# ActiveRectifier_IR1167.net
KiCad netlist of a schematic drawn in Altium Designer
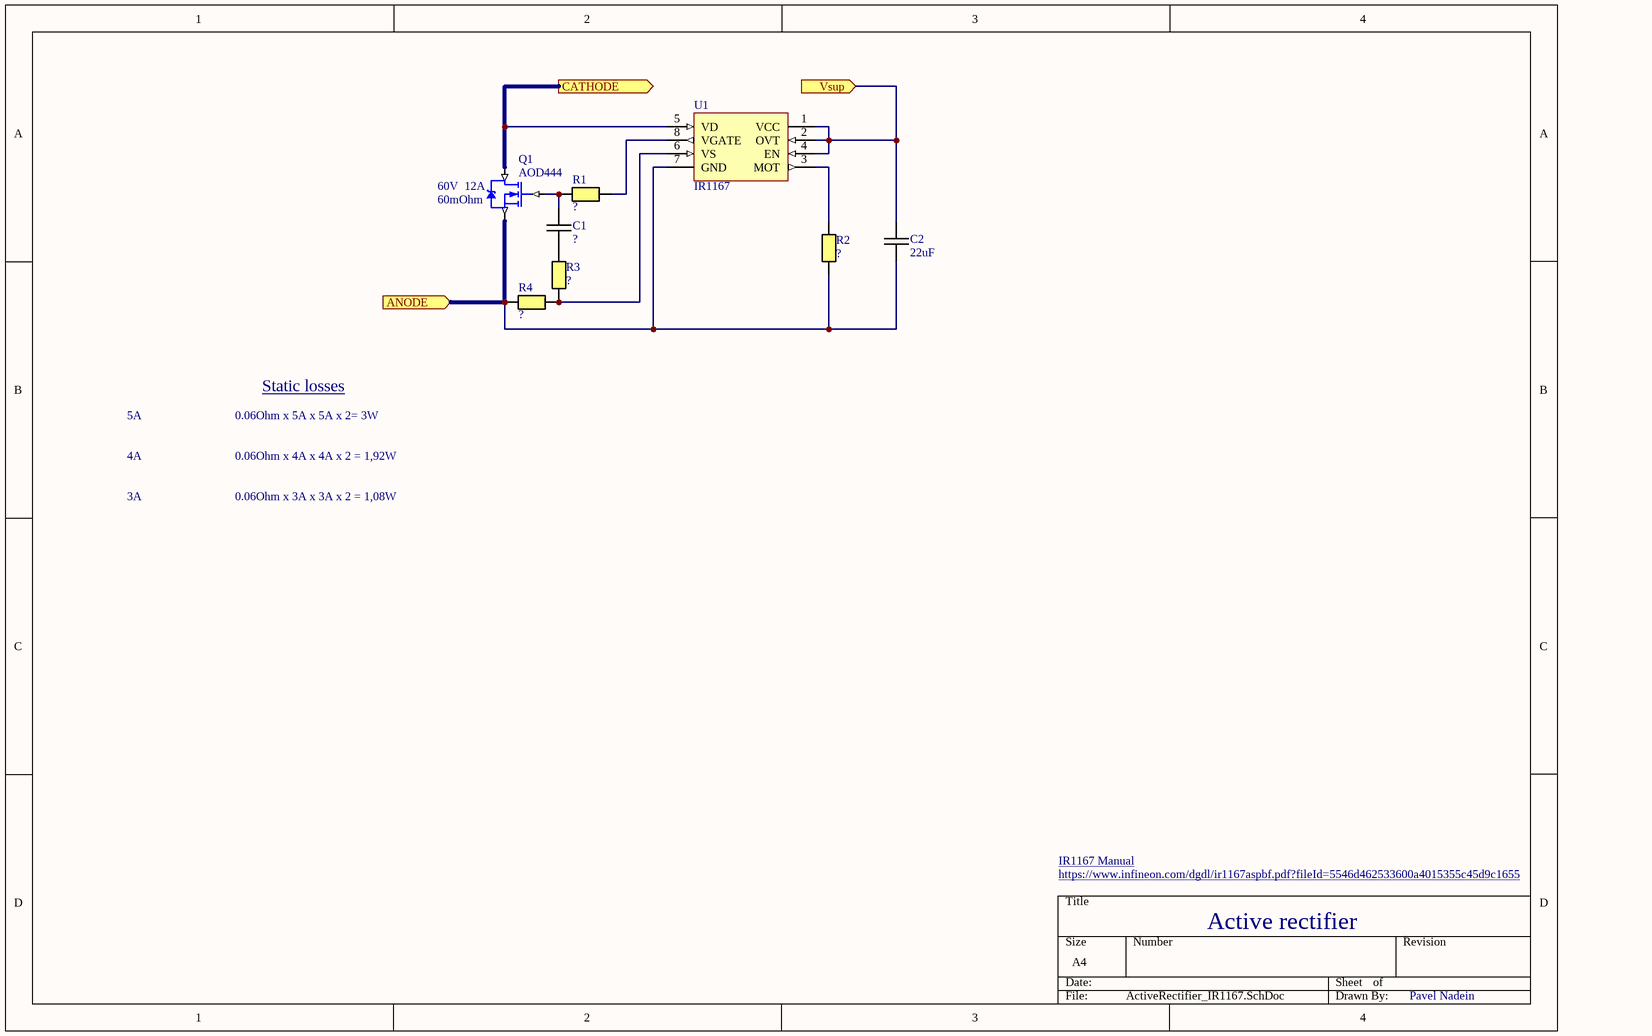
[diagram p0: ActiveRectifier_IR1167.SchDoc]

(export (version "E")
  (design (tool "Eeschema 10.0.6"))
  (components
    (comp (ref "C1")
      (value "?")
      (footprint "CAPC0603(1608)55_N")
      (description "Ceramic capacitor Medium density")
      (libsource (lib "Discrete_Passive_RCL") (part "Capacitor M"))
    )
    (comp (ref "C2")
      (value "22uF")
      (footprint "CAPC0805(2012)75_N")
      (description "Ceramic capacitor Medium density")
      (libsource (lib "Discrete_Passive_RCL") (part "Capacitor M"))
    )
    (comp (ref "Q1")
      (value "AOD444")
      (footprint "TO-252")
      (description "HEXFET Power MOSFET")
      (fields (field (name "VDS") "60V") (field (name "ID") "12A") (field (name "RDS") "60mOhm"))
      (libsource (lib "Transistors") (part "AOD444"))
    )
    (comp (ref "R1")
      (value "?")
      (footprint "RESC0603(1608)_N")
      (description "Resistor Medium Density")
      (libsource (lib "") (part "Resistor M_2"))
    )
    (comp (ref "R2")
      (value "?")
      (footprint "RESC0603(1608)_N")
      (description "Resistor Medium Density")
      (libsource (lib "") (part "Resistor M_1"))
    )
    (comp (ref "R3")
      (value "?")
      (footprint "RESC0603(1608)_N")
      (description "Resistor Medium Density")
      (libsource (lib "Discrete_Passive_RCL") (part "Resistor M"))
    )
    (comp (ref "R4")
      (value "?")
      (footprint "RESC0603(1608)_N")
      (description "Resistor Medium Density")
      (libsource (lib "") (part "Resistor M_2"))
    )
    (comp (ref "U1")
      (value "IR1167")
      (footprint "SOIC8_N")
      (description "Secondary side high speed SR controller")
      (libsource (lib "IntegrationCircuits") (part "IR1167"))
    )
  )
  (nets
    (net (code "1") (name "/ANODE") (class "Default")
      (node (ref "C2") (pin "2") (pinfunction "2_2") (pintype "passive"))
      (node (ref "Q1") (pin "3") (pinfunction "S_3") (pintype "output"))
      (node (ref "R2") (pin "1") (pinfunction "1_1") (pintype "passive"))
      (node (ref "R4") (pin "1") (pinfunction "1_1") (pintype "passive"))
      (node (ref "U1") (pin "7") (pinfunction "GND_7") (pintype "power_in"))
    )
    (net (code "2") (name "/CATHODE") (class "Default")
      (node (ref "Q1") (pin "4") (pinfunction "D_4") (pintype "input"))
      (node (ref "U1") (pin "5") (pinfunction "VD_5") (pintype "input"))
    )
    (net (code "3") (name "/Vsup") (class "Default")
      (node (ref "C2") (pin "1") (pinfunction "1_1") (pintype "passive"))
      (node (ref "U1") (pin "1") (pinfunction "VCC_1") (pintype "power_in"))
      (node (ref "U1") (pin "2") (pinfunction "OVT_2") (pintype "input"))
      (node (ref "U1") (pin "4") (pinfunction "EN_4") (pintype "input"))
    )
    (net (code "4") (name "Net-(C1-Pad2)") (class "Default")
      (node (ref "C1") (pin "2") (pinfunction "2_2") (pintype "passive"))
      (node (ref "R3") (pin "1") (pinfunction "1_1") (pintype "passive"))
    )
    (net (code "5") (name "Net-(Q1-G)") (class "Default")
      (node (ref "C1") (pin "1") (pinfunction "1_1") (pintype "passive"))
      (node (ref "Q1") (pin "1") (pinfunction "G_1") (pintype "input"))
      (node (ref "R1") (pin "1") (pinfunction "1_1") (pintype "passive"))
    )
    (net (code "6") (name "Net-(U1-MOT)") (class "Default")
      (node (ref "R2") (pin "2") (pinfunction "2_2") (pintype "passive"))
      (node (ref "U1") (pin "3") (pinfunction "MOT_3") (pintype "output"))
    )
    (net (code "7") (name "Net-(U1-VGATE)") (class "Default")
      (node (ref "R1") (pin "2") (pinfunction "2_2") (pintype "passive"))
      (node (ref "U1") (pin "8") (pinfunction "VGATE_8") (pintype "output"))
    )
    (net (code "8") (name "Net-(U1-VS)") (class "Default")
      (node (ref "R3") (pin "2") (pinfunction "2_2") (pintype "passive"))
      (node (ref "R4") (pin "2") (pinfunction "2_2") (pintype "passive"))
      (node (ref "U1") (pin "6") (pinfunction "VS_6") (pintype "input"))
    )
  )
)
